# 12V_Load_Switches.net
KiCad netlist of a schematic drawn in Altium Designer
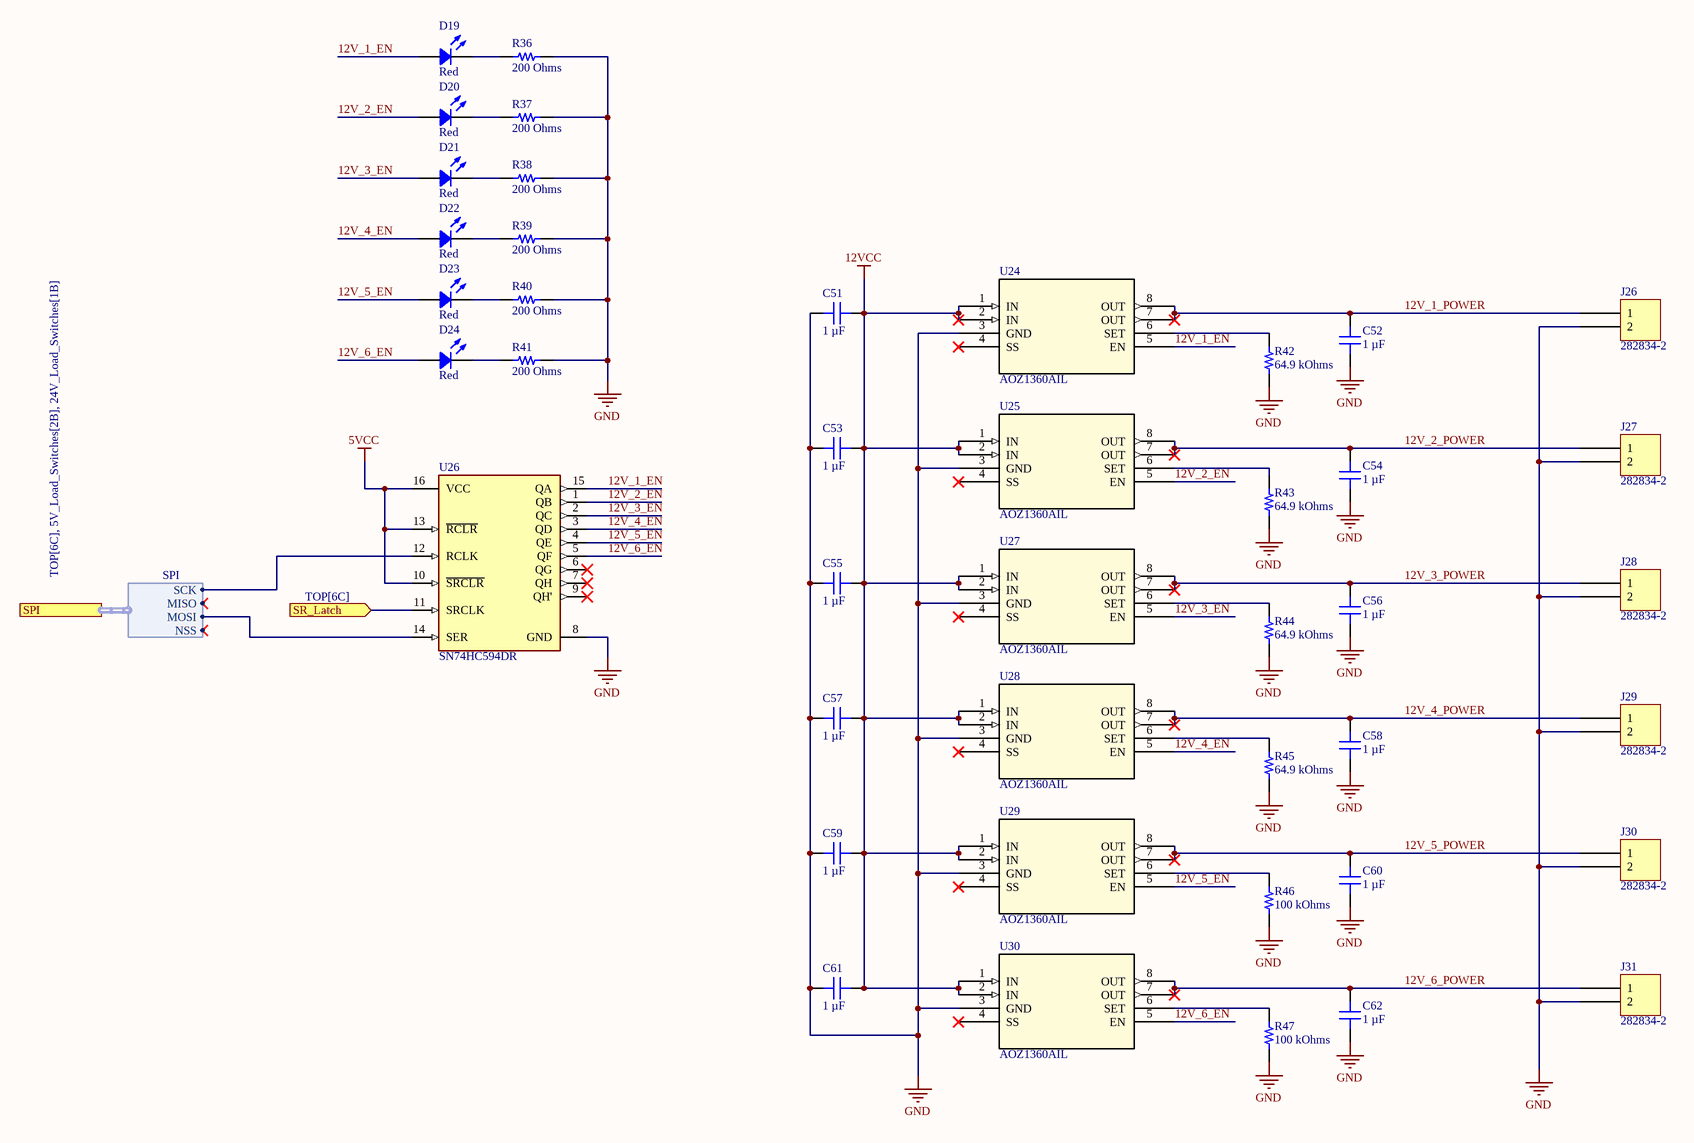
[diagram p0: 12V_Load_Switches.SchDoc]

(export (version "E")
  (design (tool "Eeschema 10.0.6"))
  (components
    (comp (ref "C51")
      (value "1 µF")
      (footprint "CAP 0805_2012")
      (description "CAP CER 1UF 50V X7R 0805")
      (fields
        (field (name "PART NUMBER") "GCJ21BR71H105KA01L")
        (field (name "MANUFACTURER") "Murata Electronics")
      )
      (libsource (lib "altium_library") (part "Capacitor"))
    )
    (comp (ref "C52")
      (value "1 µF")
      (footprint "CAP 0805_2012")
      (description "CAP CER 1UF 50V X7R 0805")
      (fields
        (field (name "PART NUMBER") "GCJ21BR71H105KA01L")
        (field (name "MANUFACTURER") "Murata Electronics")
      )
      (libsource (lib "altium_library") (part "Capacitor"))
    )
    (comp (ref "C53")
      (value "1 µF")
      (footprint "CAP 0805_2012")
      (description "CAP CER 1UF 50V X7R 0805")
      (fields
        (field (name "PART NUMBER") "GCJ21BR71H105KA01L")
        (field (name "MANUFACTURER") "Murata Electronics")
      )
      (libsource (lib "altium_library") (part "Capacitor"))
    )
    (comp (ref "C54")
      (value "1 µF")
      (footprint "CAP 0805_2012")
      (description "CAP CER 1UF 50V X7R 0805")
      (fields
        (field (name "PART NUMBER") "GCJ21BR71H105KA01L")
        (field (name "MANUFACTURER") "Murata Electronics")
      )
      (libsource (lib "altium_library") (part "Capacitor"))
    )
    (comp (ref "C55")
      (value "1 µF")
      (footprint "CAP 0805_2012")
      (description "CAP CER 1UF 50V X7R 0805")
      (fields
        (field (name "PART NUMBER") "GCJ21BR71H105KA01L")
        (field (name "MANUFACTURER") "Murata Electronics")
      )
      (libsource (lib "altium_library") (part "Capacitor"))
    )
    (comp (ref "C56")
      (value "1 µF")
      (footprint "CAP 0805_2012")
      (description "CAP CER 1UF 50V X7R 0805")
      (fields
        (field (name "PART NUMBER") "GCJ21BR71H105KA01L")
        (field (name "MANUFACTURER") "Murata Electronics")
      )
      (libsource (lib "altium_library") (part "Capacitor"))
    )
    (comp (ref "C57")
      (value "1 µF")
      (footprint "CAP 0805_2012")
      (description "CAP CER 1UF 50V X7R 0805")
      (fields
        (field (name "PART NUMBER") "GCJ21BR71H105KA01L")
        (field (name "MANUFACTURER") "Murata Electronics")
      )
      (libsource (lib "altium_library") (part "Capacitor"))
    )
    (comp (ref "C58")
      (value "1 µF")
      (footprint "CAP 0805_2012")
      (description "CAP CER 1UF 50V X7R 0805")
      (fields
        (field (name "PART NUMBER") "GCJ21BR71H105KA01L")
        (field (name "MANUFACTURER") "Murata Electronics")
      )
      (libsource (lib "altium_library") (part "Capacitor"))
    )
    (comp (ref "C59")
      (value "1 µF")
      (footprint "CAP 0805_2012")
      (description "CAP CER 1UF 50V X7R 0805")
      (fields
        (field (name "PART NUMBER") "GCJ21BR71H105KA01L")
        (field (name "MANUFACTURER") "Murata Electronics")
      )
      (libsource (lib "altium_library") (part "Capacitor"))
    )
    (comp (ref "C60")
      (value "1 µF")
      (footprint "CAP 0805_2012")
      (description "CAP CER 1UF 50V X7R 0805")
      (fields
        (field (name "PART NUMBER") "GCJ21BR71H105KA01L")
        (field (name "MANUFACTURER") "Murata Electronics")
      )
      (libsource (lib "altium_library") (part "Capacitor"))
    )
    (comp (ref "C61")
      (value "1 µF")
      (footprint "CAP 0805_2012")
      (description "CAP CER 1UF 50V X7R 0805")
      (fields
        (field (name "PART NUMBER") "GCJ21BR71H105KA01L")
        (field (name "MANUFACTURER") "Murata Electronics")
      )
      (libsource (lib "altium_library") (part "Capacitor"))
    )
    (comp (ref "C62")
      (value "1 µF")
      (footprint "CAP 0805_2012")
      (description "CAP CER 1UF 50V X7R 0805")
      (fields
        (field (name "PART NUMBER") "GCJ21BR71H105KA01L")
        (field (name "MANUFACTURER") "Murata Electronics")
      )
      (libsource (lib "altium_library") (part "Capacitor"))
    )
    (comp (ref "D19")
      (value "Red")
      (footprint "LED 0603_1608 RED")
      (description "LED RED CLEAR 2SMD")
      (fields
        (field (name "PART NUMBER") "19-213SDRC/S259/TR8")
        (field (name "MANUFACTURER") "Everlight Electronics Co Ltd")
      )
      (libsource (lib "Celestial Altium Library - altium_library") (part "LED"))
    )
    (comp (ref "D20")
      (value "Red")
      (footprint "LED 0603_1608 RED")
      (description "LED RED CLEAR 2SMD")
      (fields
        (field (name "PART NUMBER") "19-213SDRC/S259/TR8")
        (field (name "MANUFACTURER") "Everlight Electronics Co Ltd")
      )
      (libsource (lib "Celestial Altium Library - altium_library") (part "LED"))
    )
    (comp (ref "D21")
      (value "Red")
      (footprint "LED 0603_1608 RED")
      (description "LED RED CLEAR 2SMD")
      (fields
        (field (name "PART NUMBER") "19-213SDRC/S259/TR8")
        (field (name "MANUFACTURER") "Everlight Electronics Co Ltd")
      )
      (libsource (lib "Celestial Altium Library - altium_library") (part "LED"))
    )
    (comp (ref "D22")
      (value "Red")
      (footprint "LED 0603_1608 RED")
      (description "LED RED CLEAR 2SMD")
      (fields
        (field (name "PART NUMBER") "19-213SDRC/S259/TR8")
        (field (name "MANUFACTURER") "Everlight Electronics Co Ltd")
      )
      (libsource (lib "Celestial Altium Library - altium_library") (part "LED"))
    )
    (comp (ref "D23")
      (value "Red")
      (footprint "LED 0603_1608 RED")
      (description "LED RED CLEAR 2SMD")
      (fields
        (field (name "PART NUMBER") "19-213SDRC/S259/TR8")
        (field (name "MANUFACTURER") "Everlight Electronics Co Ltd")
      )
      (libsource (lib "Celestial Altium Library - altium_library") (part "LED"))
    )
    (comp (ref "D24")
      (value "Red")
      (footprint "LED 0603_1608 RED")
      (description "LED RED CLEAR 2SMD")
      (fields
        (field (name "PART NUMBER") "19-213SDRC/S259/TR8")
        (field (name "MANUFACTURER") "Everlight Electronics Co Ltd")
      )
      (libsource (lib "Celestial Altium Library - altium_library") (part "LED"))
    )
    (comp (ref "J26")
      (value "282834-2")
      (footprint "TE 282834-2")
      (description "TERM BLK 2P SIDE ENT 2.54MM PCB")
      (fields (field (name "MANUFACTURER") "TE Connectivity AMP Connectors") (field (name "VOLTAGE") "150V"))
      (libsource (lib "altium_library") (part "2 Pin"))
    )
    (comp (ref "J27")
      (value "282834-2")
      (footprint "TE 282834-2")
      (description "TERM BLK 2P SIDE ENT 2.54MM PCB")
      (fields (field (name "MANUFACTURER") "TE Connectivity AMP Connectors") (field (name "VOLTAGE") "150V"))
      (libsource (lib "altium_library") (part "2 Pin"))
    )
    (comp (ref "J28")
      (value "282834-2")
      (footprint "TE 282834-2")
      (description "TERM BLK 2P SIDE ENT 2.54MM PCB")
      (fields (field (name "MANUFACTURER") "TE Connectivity AMP Connectors") (field (name "VOLTAGE") "150V"))
      (libsource (lib "altium_library") (part "2 Pin"))
    )
    (comp (ref "J29")
      (value "282834-2")
      (footprint "TE 282834-2")
      (description "TERM BLK 2P SIDE ENT 2.54MM PCB")
      (fields (field (name "MANUFACTURER") "TE Connectivity AMP Connectors") (field (name "VOLTAGE") "150V"))
      (libsource (lib "altium_library") (part "2 Pin"))
    )
    (comp (ref "J30")
      (value "282834-2")
      (footprint "TE 282834-2")
      (description "TERM BLK 2P SIDE ENT 2.54MM PCB")
      (fields (field (name "MANUFACTURER") "TE Connectivity AMP Connectors") (field (name "VOLTAGE") "150V"))
      (libsource (lib "altium_library") (part "2 Pin"))
    )
    (comp (ref "J31")
      (value "282834-2")
      (footprint "TE 282834-2")
      (description "TERM BLK 2P SIDE ENT 2.54MM PCB")
      (fields (field (name "MANUFACTURER") "TE Connectivity AMP Connectors") (field (name "VOLTAGE") "150V"))
      (libsource (lib "altium_library") (part "2 Pin"))
    )
    (comp (ref "R36")
      (value "200 Ohms")
      (footprint "RES 0603_1608")
      (description "RES 200 OHM 0.1% 1/5W 0603")
      (fields
        (field (name "PART NUMBER") "RS73F1JTTD2000B")
        (field (name "MANUFACTURER") "KOA Speer Electronics, Inc.")
      )
      (libsource (lib "Celestial Altium Library - altium_library") (part "Resistor"))
    )
    (comp (ref "R37")
      (value "200 Ohms")
      (footprint "RES 0603_1608")
      (description "RES 200 OHM 0.1% 1/5W 0603")
      (fields
        (field (name "PART NUMBER") "RS73F1JTTD2000B")
        (field (name "MANUFACTURER") "KOA Speer Electronics, Inc.")
      )
      (libsource (lib "Celestial Altium Library - altium_library") (part "Resistor"))
    )
    (comp (ref "R38")
      (value "200 Ohms")
      (footprint "RES 0603_1608")
      (description "RES 200 OHM 0.1% 1/5W 0603")
      (fields
        (field (name "PART NUMBER") "RS73F1JTTD2000B")
        (field (name "MANUFACTURER") "KOA Speer Electronics, Inc.")
      )
      (libsource (lib "Celestial Altium Library - altium_library") (part "Resistor"))
    )
    (comp (ref "R39")
      (value "200 Ohms")
      (footprint "RES 0603_1608")
      (description "RES 200 OHM 0.1% 1/5W 0603")
      (fields
        (field (name "PART NUMBER") "RS73F1JTTD2000B")
        (field (name "MANUFACTURER") "KOA Speer Electronics, Inc.")
      )
      (libsource (lib "Celestial Altium Library - altium_library") (part "Resistor"))
    )
    (comp (ref "R40")
      (value "200 Ohms")
      (footprint "RES 0603_1608")
      (description "RES 200 OHM 0.1% 1/5W 0603")
      (fields
        (field (name "PART NUMBER") "RS73F1JTTD2000B")
        (field (name "MANUFACTURER") "KOA Speer Electronics, Inc.")
      )
      (libsource (lib "Celestial Altium Library - altium_library") (part "Resistor"))
    )
    (comp (ref "R41")
      (value "200 Ohms")
      (footprint "RES 0603_1608")
      (description "RES 200 OHM 0.1% 1/5W 0603")
      (fields
        (field (name "PART NUMBER") "RS73F1JTTD2000B")
        (field (name "MANUFACTURER") "KOA Speer Electronics, Inc.")
      )
      (libsource (lib "Celestial Altium Library - altium_library") (part "Resistor"))
    )
    (comp (ref "R42")
      (value "64.9 kOhms")
      (footprint "RES 0603_1608")
      (description "RES SMD 64.9K OHM 0.1% 1/6W 0603")
      (fields
        (field (name "PART NUMBER") "7-2176089-3")
        (field (name "MANUFACTURER") "TE Connectivity Passive Product")
      )
      (libsource (lib "altium_library") (part "Resistor"))
    )
    (comp (ref "R43")
      (value "64.9 kOhms")
      (footprint "RES 0603_1608")
      (description "RES SMD 64.9K OHM 0.1% 1/6W 0603")
      (fields
        (field (name "PART NUMBER") "7-2176089-3")
        (field (name "MANUFACTURER") "TE Connectivity Passive Product")
      )
      (libsource (lib "altium_library") (part "Resistor"))
    )
    (comp (ref "R44")
      (value "64.9 kOhms")
      (footprint "RES 0603_1608")
      (description "RES SMD 64.9K OHM 0.1% 1/6W 0603")
      (fields
        (field (name "PART NUMBER") "7-2176089-3")
        (field (name "MANUFACTURER") "TE Connectivity Passive Product")
      )
      (libsource (lib "altium_library") (part "Resistor"))
    )
    (comp (ref "R45")
      (value "64.9 kOhms")
      (footprint "RES 0603_1608")
      (description "RES SMD 64.9K OHM 0.1% 1/6W 0603")
      (fields
        (field (name "PART NUMBER") "7-2176089-3")
        (field (name "MANUFACTURER") "TE Connectivity Passive Product")
      )
      (libsource (lib "altium_library") (part "Resistor"))
    )
    (comp (ref "R46")
      (value "100 kOhms")
      (footprint "RES 0603_1608")
      (description "RES SMD 100K OHM 1% 1/10W 0603")
      (fields (field (name "PART NUMBER") "AA0603FR-07100KL") (field (name "MANUFACTURER") "Yageo"))
      (libsource (lib "altium_library") (part "Resistor"))
    )
    (comp (ref "R47")
      (value "100 kOhms")
      (footprint "RES 0603_1608")
      (description "RES SMD 100K OHM 1% 1/10W 0603")
      (fields (field (name "PART NUMBER") "AA0603FR-07100KL") (field (name "MANUFACTURER") "Yageo"))
      (libsource (lib "altium_library") (part "Resistor"))
    )
    (comp (ref "U24")
      (value "AOZ1360AIL")
      (footprint "AOZ1360AIL_AOS")
      (description "No Description Available")
      (fields (field (name "COPYRIGHT") "Copyright (C) 2023 Ultra Librarian. All rights reserved."))
      (libsource (lib "AOZ1360AIL") (part "AOZ1360AIL"))
    )
    (comp (ref "U25")
      (value "AOZ1360AIL")
      (footprint "AOZ1360AIL_AOS")
      (description "No Description Available")
      (fields (field (name "COPYRIGHT") "Copyright (C) 2023 Ultra Librarian. All rights reserved."))
      (libsource (lib "AOZ1360AIL") (part "AOZ1360AIL"))
    )
    (comp (ref "U26")
      (value "SN74HC594DR")
      (footprint "FP-D0016A-IPC_A")
      (description "IC SHIFT REGISTER 8BIT 16-SOIC")
      (libsource (lib "Altium Content Vault") (part "6ffdf0eb1487316571b39b71ede2db7"))
    )
    (comp (ref "U27")
      (value "AOZ1360AIL")
      (footprint "AOZ1360AIL_AOS")
      (description "No Description Available")
      (fields (field (name "COPYRIGHT") "Copyright (C) 2023 Ultra Librarian. All rights reserved."))
      (libsource (lib "AOZ1360AIL") (part "AOZ1360AIL"))
    )
    (comp (ref "U28")
      (value "AOZ1360AIL")
      (footprint "AOZ1360AIL_AOS")
      (description "No Description Available")
      (fields (field (name "COPYRIGHT") "Copyright (C) 2023 Ultra Librarian. All rights reserved."))
      (libsource (lib "AOZ1360AIL") (part "AOZ1360AIL"))
    )
    (comp (ref "U29")
      (value "AOZ1360AIL")
      (footprint "AOZ1360AIL_AOS")
      (description "No Description Available")
      (fields (field (name "COPYRIGHT") "Copyright (C) 2023 Ultra Librarian. All rights reserved."))
      (libsource (lib "AOZ1360AIL") (part "AOZ1360AIL"))
    )
    (comp (ref "U30")
      (value "AOZ1360AIL")
      (footprint "AOZ1360AIL_AOS")
      (description "No Description Available")
      (fields (field (name "COPYRIGHT") "Copyright (C) 2023 Ultra Librarian. All rights reserved."))
      (libsource (lib "AOZ1360AIL") (part "AOZ1360AIL"))
    )
  )
  (nets
    (net (code "2") (name "/12V_1_EN") (class "Default")
      (node (ref "D19") (pin "1") (pinfunction "1_1") (pintype "passive"))
      (node (ref "U24") (pin "5") (pinfunction "EN_5") (pintype "passive"))
      (node (ref "U26") (pin "15") (pinfunction "QA_15") (pintype "output"))
    )
    (net (code "3") (name "/12V_1_POWER") (class "Default")
      (node (ref "C52") (pin "2") (pinfunction "2_2") (pintype "passive"))
      (node (ref "J26") (pin "1") (pinfunction "1_1") (pintype "passive"))
      (node (ref "U24") (pin "7") (pinfunction "OUT_7") (pintype "output"))
      (node (ref "U24") (pin "8") (pinfunction "OUT_8") (pintype "output"))
    )
    (net (code "4") (name "/12V_2_EN") (class "Default")
      (node (ref "D20") (pin "1") (pinfunction "1_1") (pintype "passive"))
      (node (ref "U25") (pin "5") (pinfunction "EN_5") (pintype "passive"))
      (node (ref "U26") (pin "1") (pinfunction "QB_1") (pintype "output"))
    )
    (net (code "5") (name "/12V_2_POWER") (class "Default")
      (node (ref "C54") (pin "2") (pinfunction "2_2") (pintype "passive"))
      (node (ref "J27") (pin "1") (pinfunction "1_1") (pintype "passive"))
      (node (ref "U25") (pin "7") (pinfunction "OUT_7") (pintype "output"))
      (node (ref "U25") (pin "8") (pinfunction "OUT_8") (pintype "output"))
    )
    (net (code "6") (name "/12V_3_EN") (class "Default")
      (node (ref "D21") (pin "1") (pinfunction "1_1") (pintype "passive"))
      (node (ref "U26") (pin "2") (pinfunction "QC_2") (pintype "output"))
      (node (ref "U27") (pin "5") (pinfunction "EN_5") (pintype "passive"))
    )
    (net (code "7") (name "/12V_3_POWER") (class "Default")
      (node (ref "C56") (pin "2") (pinfunction "2_2") (pintype "passive"))
      (node (ref "J28") (pin "1") (pinfunction "1_1") (pintype "passive"))
      (node (ref "U27") (pin "7") (pinfunction "OUT_7") (pintype "output"))
      (node (ref "U27") (pin "8") (pinfunction "OUT_8") (pintype "output"))
    )
    (net (code "8") (name "/12V_4_EN") (class "Default")
      (node (ref "D22") (pin "1") (pinfunction "1_1") (pintype "passive"))
      (node (ref "U26") (pin "3") (pinfunction "QD_3") (pintype "output"))
      (node (ref "U28") (pin "5") (pinfunction "EN_5") (pintype "passive"))
    )
    (net (code "9") (name "/12V_4_POWER") (class "Default")
      (node (ref "C58") (pin "2") (pinfunction "2_2") (pintype "passive"))
      (node (ref "J29") (pin "1") (pinfunction "1_1") (pintype "passive"))
      (node (ref "U28") (pin "7") (pinfunction "OUT_7") (pintype "output"))
      (node (ref "U28") (pin "8") (pinfunction "OUT_8") (pintype "output"))
    )
    (net (code "10") (name "/12V_5_EN") (class "Default")
      (node (ref "D23") (pin "1") (pinfunction "1_1") (pintype "passive"))
      (node (ref "U26") (pin "4") (pinfunction "QE_4") (pintype "output"))
      (node (ref "U29") (pin "5") (pinfunction "EN_5") (pintype "passive"))
    )
    (net (code "11") (name "/12V_5_POWER") (class "Default")
      (node (ref "C60") (pin "2") (pinfunction "2_2") (pintype "passive"))
      (node (ref "J30") (pin "1") (pinfunction "1_1") (pintype "passive"))
      (node (ref "U29") (pin "7") (pinfunction "OUT_7") (pintype "output"))
      (node (ref "U29") (pin "8") (pinfunction "OUT_8") (pintype "output"))
    )
    (net (code "12") (name "/12V_6_EN") (class "Default")
      (node (ref "D24") (pin "1") (pinfunction "1_1") (pintype "passive"))
      (node (ref "U26") (pin "5") (pinfunction "QF_5") (pintype "output"))
      (node (ref "U30") (pin "5") (pinfunction "EN_5") (pintype "passive"))
    )
    (net (code "13") (name "/12V_6_POWER") (class "Default")
      (node (ref "C62") (pin "2") (pinfunction "2_2") (pintype "passive"))
      (node (ref "J31") (pin "1") (pinfunction "1_1") (pintype "passive"))
      (node (ref "U30") (pin "7") (pinfunction "OUT_7") (pintype "output"))
      (node (ref "U30") (pin "8") (pinfunction "OUT_8") (pintype "output"))
    )
    (net (code "14") (name "/MOSI") (class "Default")
      (node (ref "U26") (pin "14") (pinfunction "SER_14") (pintype "input"))
    )
    (net (code "15") (name "/SCK") (class "Default")
      (node (ref "U26") (pin "12") (pinfunction "RCLK_12") (pintype "input"))
    )
    (net (code "16") (name "/SR_Latch") (class "Default")
      (node (ref "U26") (pin "11") (pinfunction "SRCLK_11") (pintype "input"))
    )
    (net (code "18") (name "5VCC") (class "Default")
      (node (ref "U26") (pin "10") (pinfunction "~{SRCLR}_10") (pintype "input"))
      (node (ref "U26") (pin "13") (pinfunction "~{RCLR}_13") (pintype "input"))
      (node (ref "U26") (pin "16") (pinfunction "VCC_16") (pintype "power_in"))
    )
    (net (code "19") (name "12VCC") (class "Default")
      (node (ref "C51") (pin "1") (pinfunction "1_1") (pintype "passive"))
      (node (ref "C53") (pin "1") (pinfunction "1_1") (pintype "passive"))
      (node (ref "C55") (pin "1") (pinfunction "1_1") (pintype "passive"))
      (node (ref "C57") (pin "1") (pinfunction "1_1") (pintype "passive"))
      (node (ref "C59") (pin "1") (pinfunction "1_1") (pintype "passive"))
      (node (ref "C61") (pin "1") (pinfunction "1_1") (pintype "passive"))
      (node (ref "U24") (pin "1") (pinfunction "IN_1") (pintype "input"))
      (node (ref "U24") (pin "2") (pinfunction "IN_2") (pintype "input"))
      (node (ref "U25") (pin "1") (pinfunction "IN_1") (pintype "input"))
      (node (ref "U25") (pin "2") (pinfunction "IN_2") (pintype "input"))
      (node (ref "U27") (pin "1") (pinfunction "IN_1") (pintype "input"))
      (node (ref "U27") (pin "2") (pinfunction "IN_2") (pintype "input"))
      (node (ref "U28") (pin "1") (pinfunction "IN_1") (pintype "input"))
      (node (ref "U28") (pin "2") (pinfunction "IN_2") (pintype "input"))
      (node (ref "U29") (pin "1") (pinfunction "IN_1") (pintype "input"))
      (node (ref "U29") (pin "2") (pinfunction "IN_2") (pintype "input"))
      (node (ref "U30") (pin "1") (pinfunction "IN_1") (pintype "input"))
      (node (ref "U30") (pin "2") (pinfunction "IN_2") (pintype "input"))
    )
    (net (code "20") (name "GND") (class "Default")
      (node (ref "C51") (pin "2") (pinfunction "2_2") (pintype "passive"))
      (node (ref "C52") (pin "1") (pinfunction "1_1") (pintype "passive"))
      (node (ref "C53") (pin "2") (pinfunction "2_2") (pintype "passive"))
      (node (ref "C54") (pin "1") (pinfunction "1_1") (pintype "passive"))
      (node (ref "C55") (pin "2") (pinfunction "2_2") (pintype "passive"))
      (node (ref "C56") (pin "1") (pinfunction "1_1") (pintype "passive"))
      (node (ref "C57") (pin "2") (pinfunction "2_2") (pintype "passive"))
      (node (ref "C58") (pin "1") (pinfunction "1_1") (pintype "passive"))
      (node (ref "C59") (pin "2") (pinfunction "2_2") (pintype "passive"))
      (node (ref "C60") (pin "1") (pinfunction "1_1") (pintype "passive"))
      (node (ref "C61") (pin "2") (pinfunction "2_2") (pintype "passive"))
      (node (ref "C62") (pin "1") (pinfunction "1_1") (pintype "passive"))
      (node (ref "J26") (pin "2") (pinfunction "2_2") (pintype "passive"))
      (node (ref "J27") (pin "2") (pinfunction "2_2") (pintype "passive"))
      (node (ref "J28") (pin "2") (pinfunction "2_2") (pintype "passive"))
      (node (ref "J29") (pin "2") (pinfunction "2_2") (pintype "passive"))
      (node (ref "J30") (pin "2") (pinfunction "2_2") (pintype "passive"))
      (node (ref "J31") (pin "2") (pinfunction "2_2") (pintype "passive"))
      (node (ref "R36") (pin "2") (pinfunction "2_2") (pintype "passive"))
      (node (ref "R37") (pin "2") (pinfunction "2_2") (pintype "passive"))
      (node (ref "R38") (pin "2") (pinfunction "2_2") (pintype "passive"))
      (node (ref "R39") (pin "2") (pinfunction "2_2") (pintype "passive"))
      (node (ref "R40") (pin "2") (pinfunction "2_2") (pintype "passive"))
      (node (ref "R41") (pin "2") (pinfunction "2_2") (pintype "passive"))
      (node (ref "R42") (pin "1") (pinfunction "1_1") (pintype "passive"))
      (node (ref "R43") (pin "1") (pinfunction "1_1") (pintype "passive"))
      (node (ref "R44") (pin "1") (pinfunction "1_1") (pintype "passive"))
      (node (ref "R45") (pin "1") (pinfunction "1_1") (pintype "passive"))
      (node (ref "R46") (pin "1") (pinfunction "1_1") (pintype "passive"))
      (node (ref "R47") (pin "1") (pinfunction "1_1") (pintype "passive"))
      (node (ref "U24") (pin "3") (pinfunction "GND_3") (pintype "power_in"))
      (node (ref "U25") (pin "3") (pinfunction "GND_3") (pintype "power_in"))
      (node (ref "U26") (pin "8") (pinfunction "GND_8") (pintype "power_in"))
      (node (ref "U27") (pin "3") (pinfunction "GND_3") (pintype "power_in"))
      (node (ref "U28") (pin "3") (pinfunction "GND_3") (pintype "power_in"))
      (node (ref "U29") (pin "3") (pinfunction "GND_3") (pintype "power_in"))
      (node (ref "U30") (pin "3") (pinfunction "GND_3") (pintype "power_in"))
    )
    (net (code "21") (name "Net-(D19-Pad2)") (class "Default")
      (node (ref "D19") (pin "2") (pinfunction "2_2") (pintype "passive"))
      (node (ref "R36") (pin "1") (pinfunction "1_1") (pintype "passive"))
    )
    (net (code "22") (name "Net-(D20-Pad2)") (class "Default")
      (node (ref "D20") (pin "2") (pinfunction "2_2") (pintype "passive"))
      (node (ref "R37") (pin "1") (pinfunction "1_1") (pintype "passive"))
    )
    (net (code "23") (name "Net-(D21-Pad2)") (class "Default")
      (node (ref "D21") (pin "2") (pinfunction "2_2") (pintype "passive"))
      (node (ref "R38") (pin "1") (pinfunction "1_1") (pintype "passive"))
    )
    (net (code "24") (name "Net-(D22-Pad2)") (class "Default")
      (node (ref "D22") (pin "2") (pinfunction "2_2") (pintype "passive"))
      (node (ref "R39") (pin "1") (pinfunction "1_1") (pintype "passive"))
    )
    (net (code "25") (name "Net-(D23-Pad2)") (class "Default")
      (node (ref "D23") (pin "2") (pinfunction "2_2") (pintype "passive"))
      (node (ref "R40") (pin "1") (pinfunction "1_1") (pintype "passive"))
    )
    (net (code "26") (name "Net-(D24-Pad2)") (class "Default")
      (node (ref "D24") (pin "2") (pinfunction "2_2") (pintype "passive"))
      (node (ref "R41") (pin "1") (pinfunction "1_1") (pintype "passive"))
    )
    (net (code "27") (name "Net-(U24-SET)") (class "Default")
      (node (ref "R42") (pin "2") (pinfunction "2_2") (pintype "passive"))
      (node (ref "U24") (pin "6") (pinfunction "SET_6") (pintype "passive"))
    )
    (net (code "28") (name "Net-(U25-SET)") (class "Default")
      (node (ref "R43") (pin "2") (pinfunction "2_2") (pintype "passive"))
      (node (ref "U25") (pin "6") (pinfunction "SET_6") (pintype "passive"))
    )
    (net (code "29") (name "Net-(U27-SET)") (class "Default")
      (node (ref "R44") (pin "2") (pinfunction "2_2") (pintype "passive"))
      (node (ref "U27") (pin "6") (pinfunction "SET_6") (pintype "passive"))
    )
    (net (code "30") (name "Net-(U28-SET)") (class "Default")
      (node (ref "R45") (pin "2") (pinfunction "2_2") (pintype "passive"))
      (node (ref "U28") (pin "6") (pinfunction "SET_6") (pintype "passive"))
    )
    (net (code "31") (name "Net-(U29-SET)") (class "Default")
      (node (ref "R46") (pin "2") (pinfunction "2_2") (pintype "passive"))
      (node (ref "U29") (pin "6") (pinfunction "SET_6") (pintype "passive"))
    )
    (net (code "32") (name "Net-(U30-SET)") (class "Default")
      (node (ref "R47") (pin "2") (pinfunction "2_2") (pintype "passive"))
      (node (ref "U30") (pin "6") (pinfunction "SET_6") (pintype "passive"))
    )
    (net (code "33") (name "unconnected-(U24-SS-Pad4)") (class "Default")
      (node (ref "U24") (pin "4") (pinfunction "SS_4") (pintype "passive+no_connect"))
    )
    (net (code "34") (name "unconnected-(U25-SS-Pad4)") (class "Default")
      (node (ref "U25") (pin "4") (pinfunction "SS_4") (pintype "passive+no_connect"))
    )
    (net (code "35") (name "unconnected-(U26-QG-Pad6)") (class "Default")
      (node (ref "U26") (pin "6") (pinfunction "QG_6") (pintype "output+no_connect"))
    )
    (net (code "36") (name "unconnected-(U26-QH'-Pad9)") (class "Default")
      (node (ref "U26") (pin "9") (pinfunction "QH'_9") (pintype "output+no_connect"))
    )
    (net (code "37") (name "unconnected-(U26-QH-Pad7)") (class "Default")
      (node (ref "U26") (pin "7") (pinfunction "QH_7") (pintype "output+no_connect"))
    )
    (net (code "38") (name "unconnected-(U27-SS-Pad4)") (class "Default")
      (node (ref "U27") (pin "4") (pinfunction "SS_4") (pintype "passive+no_connect"))
    )
    (net (code "39") (name "unconnected-(U28-SS-Pad4)") (class "Default")
      (node (ref "U28") (pin "4") (pinfunction "SS_4") (pintype "passive+no_connect"))
    )
    (net (code "40") (name "unconnected-(U29-SS-Pad4)") (class "Default")
      (node (ref "U29") (pin "4") (pinfunction "SS_4") (pintype "passive+no_connect"))
    )
    (net (code "41") (name "unconnected-(U30-SS-Pad4)") (class "Default")
      (node (ref "U30") (pin "4") (pinfunction "SS_4") (pintype "passive+no_connect"))
    )
  )
)
